# TopSheet.net
KiCad netlist of a schematic drawn in Altium Designer
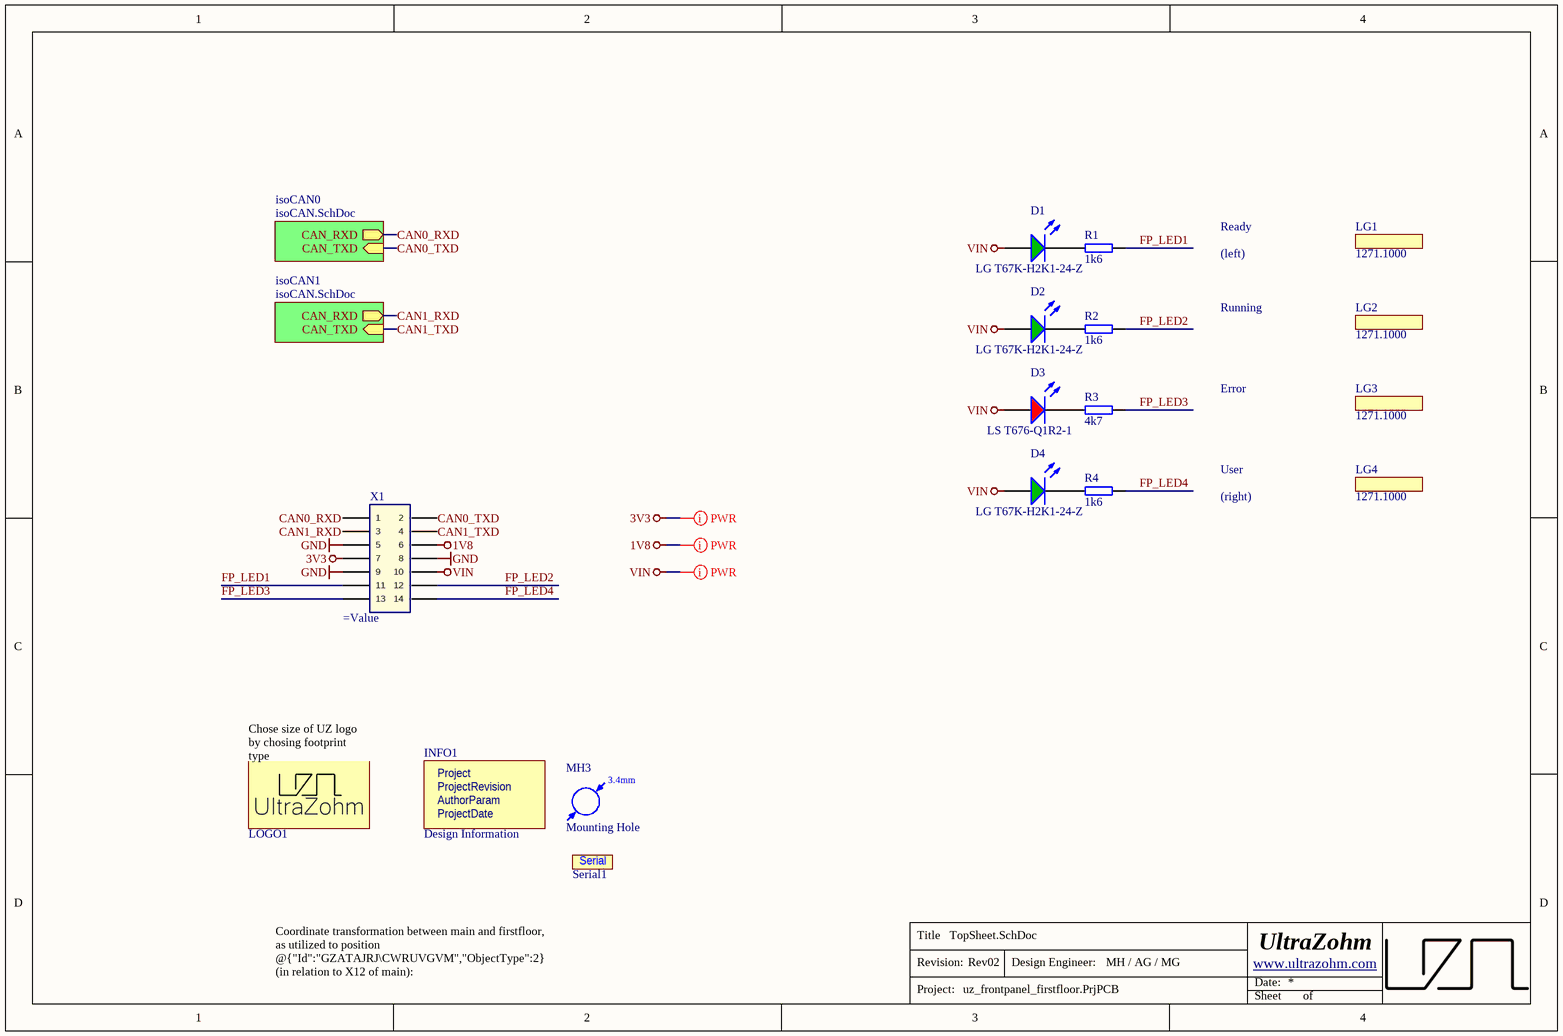
[diagram p0: TopSheet.SchDoc]

(export (version "E")
  (design (tool "Eeschema 10.0.6"))
  (components
    (comp (ref "D1")
      (value "LG T67K-H2K1-24-Z")
      (footprint "FP-LS_T676-Q1R2-1-Z-MFG")
      (description "Standard LEDs - SMD Green, 570nm 9mcd, 2mA")
      (fields
        (field (name "MANUFACTURER") "OSRAM Opto Semicon")
        (field (name "LCSC PART NUMBER") "C5248446")
        (field (name "CREATED FROM") "FRosner")
      )
      (libsource (lib "user") (part "LED_Green"))
    )
    (comp (ref "D2")
      (value "LG T67K-H2K1-24-Z")
      (footprint "FP-LS_T676-Q1R2-1-Z-MFG")
      (description "Standard LEDs - SMD Green, 570nm 9mcd, 2mA")
      (fields
        (field (name "MANUFACTURER") "OSRAM Opto Semicon")
        (field (name "LCSC PART NUMBER") "C5248446")
        (field (name "CREATED FROM") "FRosner")
      )
      (libsource (lib "user") (part "LED_Green"))
    )
    (comp (ref "D3")
      (value "LS T676-Q1R2-1")
      (footprint "FP-LS_T676-Q1R2-1-Z-MFG")
      (description "Standard LEDs - SMD Super Red, 645nm 180mcd, 20mA")
      (fields
        (field (name "MANUFACTURER") "OSRAM Opto Semicon")
        (field (name "LCSC PART NUMBER") "C19360690")
        (field (name "CREATED FROM") "FRosner")
      )
      (libsource (lib "user") (part "LED_Red"))
    )
    (comp (ref "D4")
      (value "LG T67K-H2K1-24-Z")
      (footprint "FP-LS_T676-Q1R2-1-Z-MFG")
      (description "Standard LEDs - SMD Green, 570nm 9mcd, 2mA")
      (fields
        (field (name "MANUFACTURER") "OSRAM Opto Semicon")
        (field (name "LCSC PART NUMBER") "C5248446")
        (field (name "CREATED FROM") "FRosner")
      )
      (libsource (lib "user") (part "LED_Green"))
    )
    (comp (ref "INFO1")
      (value "Design Information")
      (footprint "Design_info")
      (fields (field (name "MANUFACTURER") "UltraZohm") (field (name "CREATED FROM") "MGremer"))
      (libsource (lib "user") (part "Design_info"))
    )
    (comp (ref "LG1")
      (value "1271.1000")
      (footprint "1271.1000")
      (description "Light guide, horizontal, 18.29 mm, 1 rod, round, PCB mounting, transparent")
      (fields
        (field (name "MANUFACTURER") "MENTOR")
        (field (name "LCSC PART NUMBER") "C22441102")
        (field (name "CREATED FROM") "FRosner")
      )
      (libsource (lib "user") (part "Lightguide"))
    )
    (comp (ref "LG2")
      (value "1271.1000")
      (footprint "1271.1000")
      (description "Light guide, horizontal, 18.29 mm, 1 rod, round, PCB mounting, transparent")
      (fields
        (field (name "MANUFACTURER") "MENTOR")
        (field (name "LCSC PART NUMBER") "C22441102")
        (field (name "CREATED FROM") "FRosner")
      )
      (libsource (lib "user") (part "Lightguide"))
    )
    (comp (ref "LG3")
      (value "1271.1000")
      (footprint "1271.1000")
      (description "Light guide, horizontal, 18.29 mm, 1 rod, round, PCB mounting, transparent")
      (fields
        (field (name "MANUFACTURER") "MENTOR")
        (field (name "LCSC PART NUMBER") "C22441102")
        (field (name "CREATED FROM") "FRosner")
      )
      (libsource (lib "user") (part "Lightguide"))
    )
    (comp (ref "LG4")
      (value "1271.1000")
      (footprint "1271.1000")
      (description "Light guide, horizontal, 18.29 mm, 1 rod, round, PCB mounting, transparent")
      (fields
        (field (name "MANUFACTURER") "MENTOR")
        (field (name "LCSC PART NUMBER") "C22441102")
        (field (name "CREATED FROM") "FRosner")
      )
      (libsource (lib "user") (part "Lightguide"))
    )
    (comp (ref "LOGO1")
      (value "UZ Logo")
      (footprint "UZ_Logo_small")
      (description "Official Project Logo of the UltraZohm")
      (fields
        (field (name "MANUFACTURER") "PCB Manufacturer")
        (field (name "MANUFACTURER PART NUMBER") "UltraZohm Logo")
        (field (name "CREATED FROM") "T. Wendt")
      )
      (libsource (lib "user") (part "UZ_LOGO"))
    )
    (comp (ref "MH3")
      (value "Mounting Hole")
      (footprint "MH_3.4")
      (fields (field (name "CREATED FROM") "MHlatky"))
      (libsource (lib "user") (part "Mounting Hole"))
    )
    (comp (ref "R1")
      (value "1k6")
      (footprint "R_1206_TE")
      (description "Generic resistor")
      (fields
        (field (name "MANUFACTURER PART NUMBER") "UZgen_R_1206_1k6")
        (field (name "MANUFACTURER") "UZgen")
        (field (name "CREATED FROM") "UZgenTool")
      )
      (libsource (lib "user") (part "RES"))
    )
    (comp (ref "R2")
      (value "1k6")
      (footprint "R_1206_TE")
      (description "Generic resistor")
      (fields
        (field (name "MANUFACTURER PART NUMBER") "UZgen_R_1206_1k6")
        (field (name "MANUFACTURER") "UZgen")
        (field (name "CREATED FROM") "UZgenTool")
      )
      (libsource (lib "user") (part "RES"))
    )
    (comp (ref "R3")
      (value "4k7")
      (footprint "R_1206_TE")
      (description "Generic resistor")
      (fields
        (field (name "MANUFACTURER PART NUMBER") "UZgen_R_1206_4k7")
        (field (name "MANUFACTURER") "UZgen")
        (field (name "CREATED FROM") "UZgenTool")
      )
      (libsource (lib "user") (part "RES"))
    )
    (comp (ref "R4")
      (value "1k6")
      (footprint "R_1206_TE")
      (description "Generic resistor")
      (fields
        (field (name "MANUFACTURER PART NUMBER") "UZgen_R_1206_1k6")
        (field (name "MANUFACTURER") "UZgen")
        (field (name "CREATED FROM") "UZgenTool")
      )
      (libsource (lib "user") (part "RES"))
    )
    (comp (ref "Serial1")
      (value "Serial #")
      (footprint "SERIAL")
      (description "Field to put in a serial number")
      (fields
        (field (name "MANUFACTURER") "PCB Manufacturer")
        (field (name "MANUFACTURER PART NUMBER") "Serial Number")
        (field (name "CREATED FROM") "T. Wendt")
      )
      (libsource (lib "user") (part "SerialNumber"))
    )
    (comp (ref "X1")
      (value "~")
      (footprint "MTSW-107-11-T-D-740")
      (description "Headers & Wire Housings Classic PCB Header Strips, 0.100\" pitch")
      (fields
        (field (name "MANUFACTURER PART NUMBER") "MTSW-107-11-T-D-740")
        (field (name "MANUFACTURER") "SAMTEC")
        (field (name "CREATED FROM") "FRosner")
      )
      (libsource (lib "user") (part "TSW-107-07-S-D"))
    )
  )
  (nets
    (net (code "1") (name "/CAN0_RXD") (class "Default")
      (node (ref "X1") (pin "1") (pinfunction "1_1") (pintype "passive"))
    )
    (net (code "2") (name "/CAN0_TXD") (class "Default")
      (node (ref "X1") (pin "2") (pinfunction "2_2") (pintype "passive"))
    )
    (net (code "3") (name "/CAN1_RXD") (class "Default")
      (node (ref "X1") (pin "3") (pinfunction "3_3") (pintype "passive"))
    )
    (net (code "4") (name "/CAN1_TXD") (class "Default")
      (node (ref "X1") (pin "4") (pinfunction "4_4") (pintype "passive"))
    )
    (net (code "5") (name "/FP_LED1") (class "Default")
      (node (ref "R1") (pin "2") (pinfunction "2_2") (pintype "passive"))
      (node (ref "X1") (pin "11") (pinfunction "11_11") (pintype "passive"))
    )
    (net (code "6") (name "/FP_LED2") (class "Default")
      (node (ref "R2") (pin "2") (pinfunction "2_2") (pintype "passive"))
      (node (ref "X1") (pin "12") (pinfunction "12_12") (pintype "passive"))
    )
    (net (code "7") (name "/FP_LED3") (class "Default")
      (node (ref "R3") (pin "2") (pinfunction "2_2") (pintype "passive"))
      (node (ref "X1") (pin "13") (pinfunction "13_13") (pintype "passive"))
    )
    (net (code "8") (name "/FP_LED4") (class "Default")
      (node (ref "R4") (pin "2") (pinfunction "2_2") (pintype "passive"))
      (node (ref "X1") (pin "14") (pinfunction "14_14") (pintype "passive"))
    )
    (net (code "9") (name "1V8") (class "Default")
      (node (ref "X1") (pin "6") (pinfunction "6_6") (pintype "passive"))
    )
    (net (code "10") (name "3V3") (class "Default")
      (node (ref "X1") (pin "7") (pinfunction "7_7") (pintype "passive"))
    )
    (net (code "11") (name "GND") (class "Default")
      (node (ref "X1") (pin "5") (pinfunction "5_5") (pintype "passive"))
      (node (ref "X1") (pin "8") (pinfunction "8_8") (pintype "passive"))
      (node (ref "X1") (pin "9") (pinfunction "9_9") (pintype "passive"))
    )
    (net (code "12") (name "Net-(D1-K)") (class "Default")
      (node (ref "D1") (pin "1") (pinfunction "K_1") (pintype "passive"))
      (node (ref "R1") (pin "1") (pinfunction "1_1") (pintype "passive"))
    )
    (net (code "13") (name "Net-(D2-K)") (class "Default")
      (node (ref "D2") (pin "1") (pinfunction "K_1") (pintype "passive"))
      (node (ref "R2") (pin "1") (pinfunction "1_1") (pintype "passive"))
    )
    (net (code "14") (name "Net-(D3-K)") (class "Default")
      (node (ref "D3") (pin "1") (pinfunction "K_1") (pintype "passive"))
      (node (ref "R3") (pin "1") (pinfunction "1_1") (pintype "passive"))
    )
    (net (code "15") (name "Net-(D4-K)") (class "Default")
      (node (ref "D4") (pin "1") (pinfunction "K_1") (pintype "passive"))
      (node (ref "R4") (pin "1") (pinfunction "1_1") (pintype "passive"))
    )
    (net (code "16") (name "VIN") (class "Default")
      (node (ref "D1") (pin "2") (pinfunction "A_2") (pintype "passive"))
      (node (ref "D2") (pin "2") (pinfunction "A_2") (pintype "passive"))
      (node (ref "D3") (pin "2") (pinfunction "A_2") (pintype "passive"))
      (node (ref "D4") (pin "2") (pinfunction "A_2") (pintype "passive"))
      (node (ref "X1") (pin "10") (pinfunction "10_10") (pintype "passive"))
    )
  )
)
